# openTPM-v14.net
KiCad netlist of a schematic drawn in EAGLE
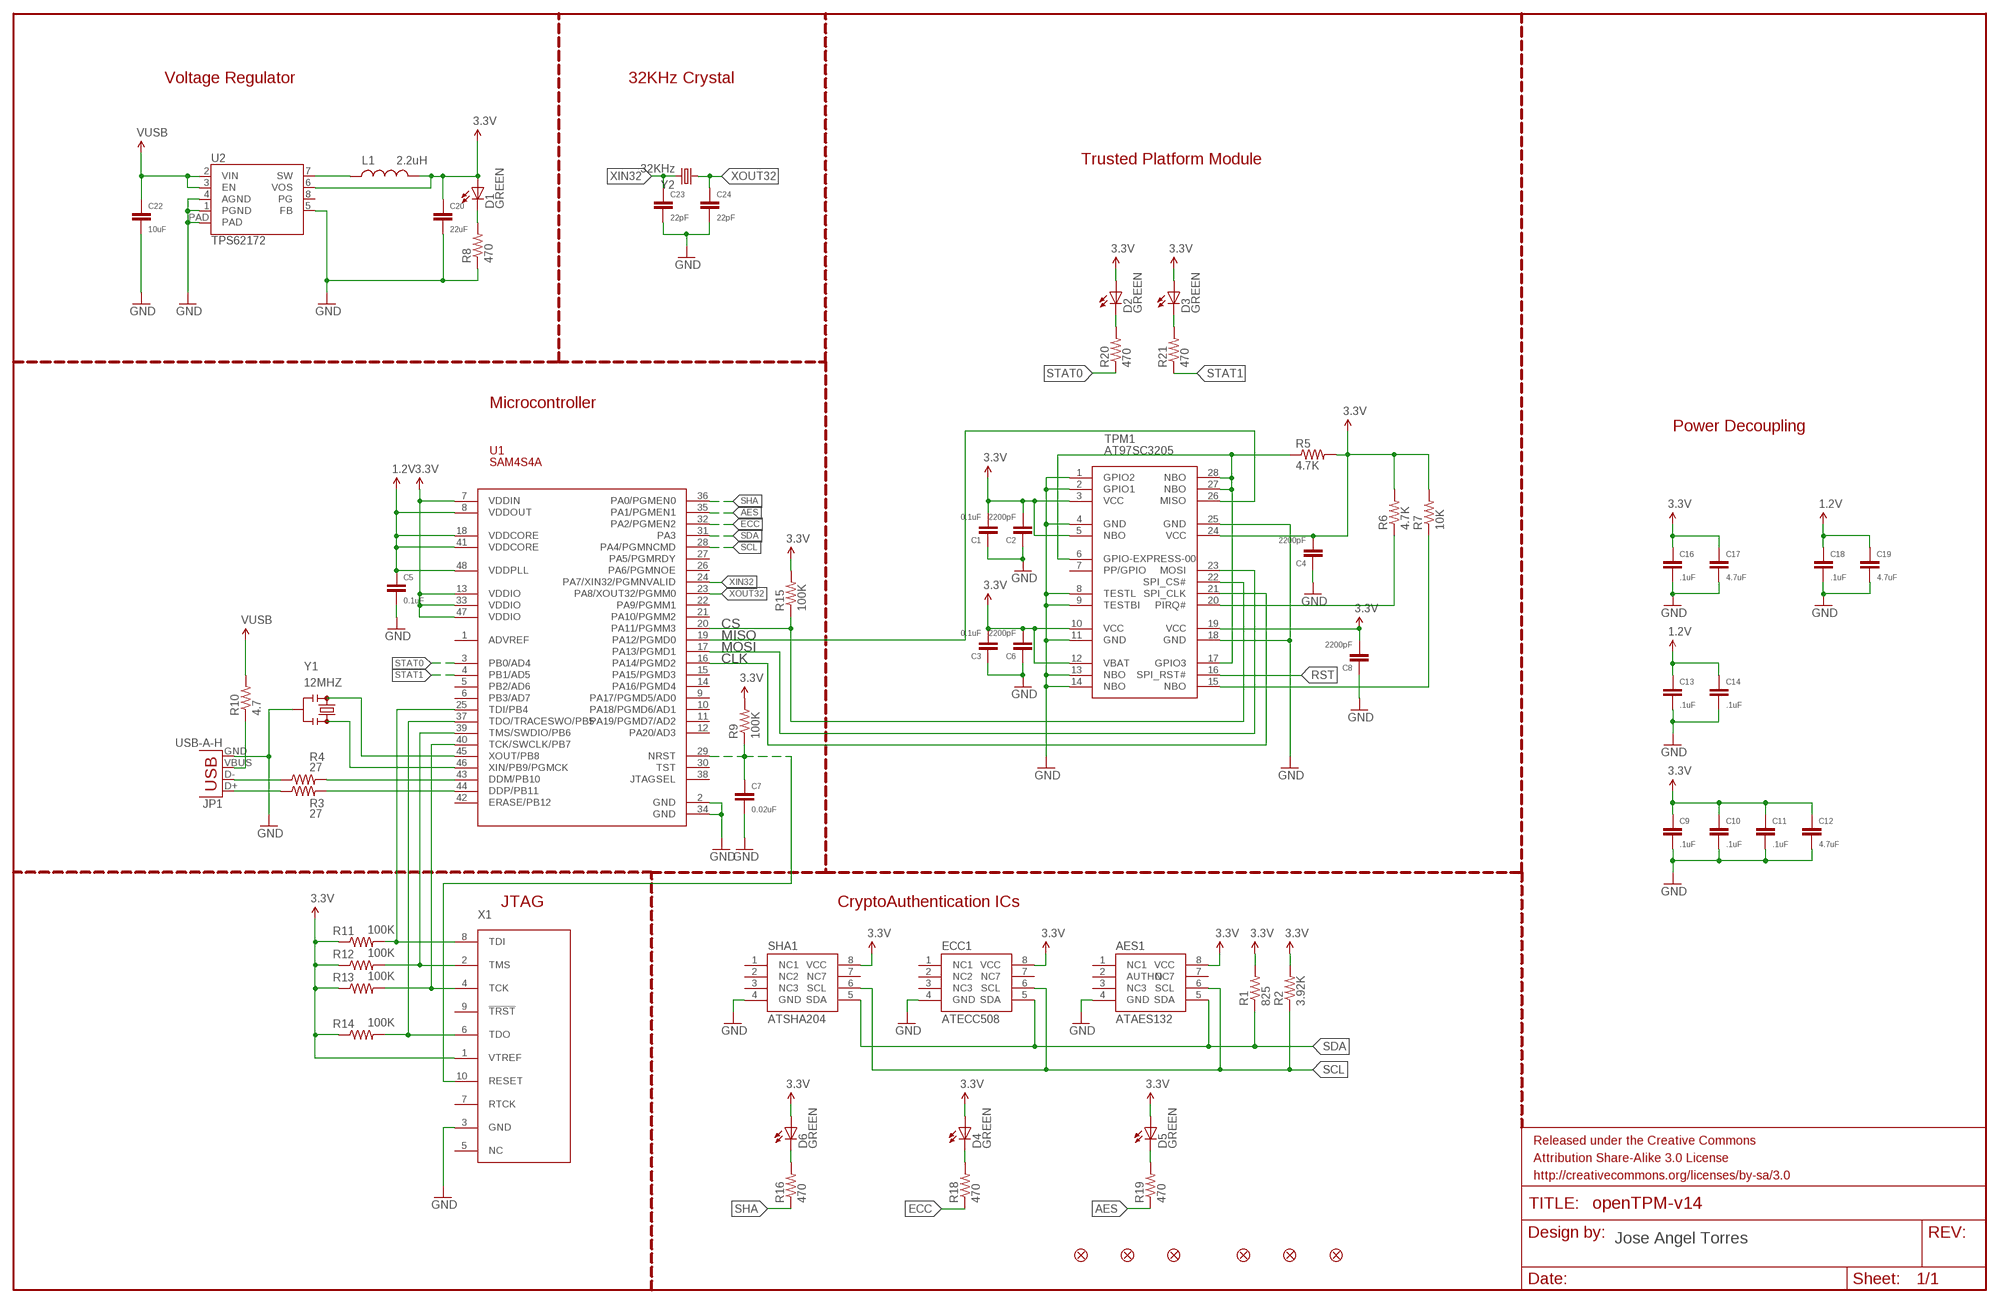
[diagram p0: schematic, sheet 1]

(export (version "E")
  (design (tool "Eeschema 10.0.6"))
  (components
    (comp (ref "AES1")
      (value "ATAES132")
      (footprint "eagle-import:CRYPTOTRONIX_SOIC8")
      (libsource (lib "eagle-import") (part "CRYPTOTRONIX_ATAES132"))
    )
    (comp (ref "C1")
      (value "0.1uF")
      (footprint "eagle-import:0402")
      (libsource (lib "eagle-import") (part "CAPACITOR.0402"))
    )
    (comp (ref "C2")
      (value "2200pF")
      (footprint "eagle-import:0402")
      (libsource (lib "eagle-import") (part "CAPACITOR.0402"))
    )
    (comp (ref "C3")
      (value "0.1uF")
      (footprint "eagle-import:0402")
      (libsource (lib "eagle-import") (part "CAPACITOR.0402"))
    )
    (comp (ref "C4")
      (value "2200pF")
      (footprint "eagle-import:0402")
      (libsource (lib "eagle-import") (part "CAPACITOR.0402"))
    )
    (comp (ref "C5")
      (value "0.1uF")
      (footprint "eagle-import:0402")
      (libsource (lib "eagle-import") (part "CAPACITOR.0402"))
    )
    (comp (ref "C6")
      (value "2200pF")
      (footprint "eagle-import:0402")
      (libsource (lib "eagle-import") (part "CAPACITOR.0402"))
    )
    (comp (ref "C7")
      (value "0.02uF")
      (footprint "eagle-import:0402")
      (libsource (lib "eagle-import") (part "CAPACITOR.0402"))
    )
    (comp (ref "C8")
      (value "2200pF")
      (footprint "eagle-import:0402")
      (libsource (lib "eagle-import") (part "CAPACITOR.0402"))
    )
    (comp (ref "C9")
      (value ".1uF")
      (footprint "eagle-import:0402")
      (libsource (lib "eagle-import") (part "CAPACITOR.0402"))
    )
    (comp (ref "C10")
      (value ".1uF")
      (footprint "eagle-import:0402")
      (libsource (lib "eagle-import") (part "CAPACITOR.0402"))
    )
    (comp (ref "C11")
      (value ".1uF")
      (footprint "eagle-import:0402")
      (libsource (lib "eagle-import") (part "CAPACITOR.0402"))
    )
    (comp (ref "C12")
      (value "4.7uF")
      (footprint "eagle-import:0402")
      (libsource (lib "eagle-import") (part "CAPACITOR.0402"))
    )
    (comp (ref "C13")
      (value ".1uF")
      (footprint "eagle-import:0402")
      (libsource (lib "eagle-import") (part "CAPACITOR.0402"))
    )
    (comp (ref "C14")
      (value ".1uF")
      (footprint "eagle-import:0402")
      (libsource (lib "eagle-import") (part "CAPACITOR.0402"))
    )
    (comp (ref "C16")
      (value ".1uF")
      (footprint "eagle-import:0402")
      (libsource (lib "eagle-import") (part "CAPACITOR.0402"))
    )
    (comp (ref "C17")
      (value "4.7uF")
      (footprint "eagle-import:0402")
      (libsource (lib "eagle-import") (part "CAPACITOR.0402"))
    )
    (comp (ref "C18")
      (value ".1uF")
      (footprint "eagle-import:0402")
      (libsource (lib "eagle-import") (part "CAPACITOR.0402"))
    )
    (comp (ref "C19")
      (value "4.7uF")
      (footprint "eagle-import:0402")
      (libsource (lib "eagle-import") (part "CAPACITOR.0402"))
    )
    (comp (ref "C20")
      (value "22uF")
      (footprint "eagle-import:0603")
      (libsource (lib "eagle-import") (part "CAPACITOR.0603"))
    )
    (comp (ref "C22")
      (value "10uF")
      (footprint "eagle-import:0402")
      (libsource (lib "eagle-import") (part "CAPACITOR.0402"))
    )
    (comp (ref "C23")
      (value "22pF")
      (footprint "eagle-import:0402")
      (libsource (lib "eagle-import") (part "CAPACITOR.0402"))
    )
    (comp (ref "C24")
      (value "22pF")
      (footprint "eagle-import:0402")
      (libsource (lib "eagle-import") (part "CAPACITOR.0402"))
    )
    (comp (ref "D1")
      (value "GREEN")
      (footprint "eagle-import:SPARKFUN-LED_LED-0603")
      (libsource (lib "eagle-import") (part "SPARKFUN-LED_LED-GREEN0603"))
    )
    (comp (ref "D2")
      (value "GREEN")
      (footprint "eagle-import:SPARKFUN-LED_LED-0603")
      (libsource (lib "eagle-import") (part "SPARKFUN-LED_LED-GREEN0603"))
    )
    (comp (ref "D3")
      (value "GREEN")
      (footprint "eagle-import:SPARKFUN-LED_LED-0603")
      (libsource (lib "eagle-import") (part "SPARKFUN-LED_LED-GREEN0603"))
    )
    (comp (ref "D4")
      (value "GREEN")
      (footprint "eagle-import:SPARKFUN-LED_LED-0603")
      (libsource (lib "eagle-import") (part "SPARKFUN-LED_LED-GREEN0603"))
    )
    (comp (ref "D5")
      (value "GREEN")
      (footprint "eagle-import:SPARKFUN-LED_LED-0603")
      (libsource (lib "eagle-import") (part "SPARKFUN-LED_LED-GREEN0603"))
    )
    (comp (ref "D6")
      (value "GREEN")
      (footprint "eagle-import:SPARKFUN-LED_LED-0603")
      (libsource (lib "eagle-import") (part "SPARKFUN-LED_LED-GREEN0603"))
    )
    (comp (ref "ECC1")
      (value "ATECC508")
      (footprint "eagle-import:CRYPTOTRONIX_SOIC8")
      (libsource (lib "eagle-import") (part "ATECC508"))
    )
    (comp (ref "FID1")
      (value "SPARKFUN-AESTHETICS_FIDUCIAL1X2")
      (footprint "eagle-import:SPARKFUN-AESTHETICS_FIDUCIAL-1X2")
      (libsource (lib "eagle-import") (part "SPARKFUN-AESTHETICS_FIDUCIAL1X2"))
    )
    (comp (ref "FID2")
      (value "SPARKFUN-AESTHETICS_FIDUCIAL1X2")
      (footprint "eagle-import:SPARKFUN-AESTHETICS_FIDUCIAL-1X2")
      (libsource (lib "eagle-import") (part "SPARKFUN-AESTHETICS_FIDUCIAL1X2"))
    )
    (comp (ref "FID3")
      (value "SPARKFUN-AESTHETICS_FIDUCIAL1X2")
      (footprint "eagle-import:SPARKFUN-AESTHETICS_FIDUCIAL-1X2")
      (libsource (lib "eagle-import") (part "SPARKFUN-AESTHETICS_FIDUCIAL1X2"))
    )
    (comp (ref "FID4")
      (value "SPARKFUN-AESTHETICS_FIDUCIAL1X2")
      (footprint "eagle-import:SPARKFUN-AESTHETICS_FIDUCIAL-1X2")
      (libsource (lib "eagle-import") (part "SPARKFUN-AESTHETICS_FIDUCIAL1X2"))
    )
    (comp (ref "FID5")
      (value "SPARKFUN-AESTHETICS_FIDUCIAL1X2")
      (footprint "eagle-import:SPARKFUN-AESTHETICS_FIDUCIAL-1X2")
      (libsource (lib "eagle-import") (part "SPARKFUN-AESTHETICS_FIDUCIAL1X2"))
    )
    (comp (ref "FID6")
      (value "SPARKFUN-AESTHETICS_FIDUCIAL1X2")
      (footprint "eagle-import:SPARKFUN-AESTHETICS_FIDUCIAL-1X2")
      (libsource (lib "eagle-import") (part "SPARKFUN-AESTHETICS_FIDUCIAL1X2"))
    )
    (comp (ref "JP1")
      (value "USB-A-H")
      (footprint "eagle-import:USB-A-H")
      (libsource (lib "eagle-import") (part "USB-A-H"))
    )
    (comp (ref "L1")
      (value "2.2uH")
      (footprint "eagle-import:C0402")
      (libsource (lib "eagle-import") (part "INDUCTOR0402"))
    )
    (comp (ref "R1")
      (value "825")
      (footprint "eagle-import:0402")
      (libsource (lib "eagle-import") (part "RESISTOR.0402"))
    )
    (comp (ref "R2")
      (value "3.92K")
      (footprint "eagle-import:0402")
      (libsource (lib "eagle-import") (part "RESISTOR.0402"))
    )
    (comp (ref "R3")
      (value "27")
      (footprint "eagle-import:0402")
      (libsource (lib "eagle-import") (part "RESISTOR.0402"))
    )
    (comp (ref "R4")
      (value "27")
      (footprint "eagle-import:0402")
      (libsource (lib "eagle-import") (part "RESISTOR.0402"))
    )
    (comp (ref "R5")
      (value "4.7K")
      (footprint "eagle-import:0402")
      (libsource (lib "eagle-import") (part "RESISTOR.0402"))
    )
    (comp (ref "R6")
      (value "4.7K")
      (footprint "eagle-import:0402")
      (libsource (lib "eagle-import") (part "RESISTOR.0402"))
    )
    (comp (ref "R7")
      (value "10K")
      (footprint "eagle-import:0402")
      (libsource (lib "eagle-import") (part "RESISTOR.0402"))
    )
    (comp (ref "R8")
      (value "470")
      (footprint "eagle-import:0402")
      (libsource (lib "eagle-import") (part "RESISTOR.0402"))
    )
    (comp (ref "R9")
      (value "100K")
      (footprint "eagle-import:0402")
      (libsource (lib "eagle-import") (part "RESISTOR.0402"))
    )
    (comp (ref "R10")
      (value "4.7")
      (footprint "eagle-import:0402")
      (libsource (lib "eagle-import") (part "RESISTOR.0402"))
    )
    (comp (ref "R11")
      (value "100K")
      (footprint "eagle-import:0402")
      (libsource (lib "eagle-import") (part "RESISTOR.0402"))
    )
    (comp (ref "R12")
      (value "100K")
      (footprint "eagle-import:0402")
      (libsource (lib "eagle-import") (part "RESISTOR.0402"))
    )
    (comp (ref "R13")
      (value "100K")
      (footprint "eagle-import:0402")
      (libsource (lib "eagle-import") (part "RESISTOR.0402"))
    )
    (comp (ref "R14")
      (value "100K")
      (footprint "eagle-import:0402")
      (libsource (lib "eagle-import") (part "RESISTOR.0402"))
    )
    (comp (ref "R15")
      (value "100K")
      (footprint "eagle-import:0402")
      (libsource (lib "eagle-import") (part "RESISTOR.0402"))
    )
    (comp (ref "R16")
      (value "470")
      (footprint "eagle-import:0402")
      (libsource (lib "eagle-import") (part "RESISTOR.0402"))
    )
    (comp (ref "R18")
      (value "470")
      (footprint "eagle-import:0402")
      (libsource (lib "eagle-import") (part "RESISTOR.0402"))
    )
    (comp (ref "R19")
      (value "470")
      (footprint "eagle-import:0402")
      (libsource (lib "eagle-import") (part "RESISTOR.0402"))
    )
    (comp (ref "R20")
      (value "470")
      (footprint "eagle-import:0402")
      (libsource (lib "eagle-import") (part "RESISTOR.0402"))
    )
    (comp (ref "R21")
      (value "470")
      (footprint "eagle-import:0402")
      (libsource (lib "eagle-import") (part "RESISTOR.0402"))
    )
    (comp (ref "SHA1")
      (value "ATSHA204")
      (footprint "eagle-import:CRYPTOTRONIX_SOIC8")
      (libsource (lib "eagle-import") (part "CRYPTOTRONIX_ATSHA204"))
    )
    (comp (ref "TPM1")
      (value "AT97SC3205")
      (footprint "eagle-import:TSSOP28")
      (libsource (lib "eagle-import") (part "AT97SC3205"))
    )
    (comp (ref "U1")
      (value "SAM4S4A")
      (footprint "eagle-import:LQFP-48")
      (libsource (lib "eagle-import") (part "SAM4S4A"))
    )
    (comp (ref "U2")
      (value "TPS62172")
      (footprint "eagle-import:WSON-8-PAD")
      (libsource (lib "eagle-import") (part "TPS62172"))
    )
    (comp (ref "X1")
      (value "TC2050-NL-MCP-NL")
      (footprint "eagle-import:TC2030-MCP-NL")
      (libsource (lib "eagle-import") (part "TC2050-NL-MCP-NL"))
    )
    (comp (ref "Y1")
      (value "12MHZ")
      (footprint "eagle-import:RESONATOR-SMD")
      (libsource (lib "eagle-import") (part "RESONATOR12MHZ"))
    )
    (comp (ref "Y2")
      (value "32KHz")
      (footprint "eagle-import:CRYSTAL-32KHZ-SMD_EPSON_MC146")
      (libsource (lib "eagle-import") (part "CRYSTALEPSONMC146"))
    )
  )
  (nets
    (net (code "1") (name "/CLK") (class "Default")
      (node (ref "TPM1") (pin "21") (pinfunction "SPI_CLK_21") (pintype "bidirectional"))
      (node (ref "U1") (pin "16") (pinfunction "PA14/PGMD2_16") (pintype "bidirectional"))
    )
    (net (code "2") (name "/CS") (class "Default")
      (node (ref "R15") (pin "1") (pinfunction "1_1") (pintype "passive"))
      (node (ref "TPM1") (pin "22") (pinfunction "SPI_CS#_22") (pintype "power_in"))
      (node (ref "U1") (pin "20") (pinfunction "PA11/PGMM3_20") (pintype "bidirectional"))
    )
    (net (code "3") (name "/MISO") (class "Default")
      (node (ref "TPM1") (pin "26") (pinfunction "MISO_26") (pintype "power_in"))
      (node (ref "U1") (pin "19") (pinfunction "PA12/PGMD0_19") (pintype "bidirectional"))
    )
    (net (code "4") (name "/MOSI") (class "Default")
      (node (ref "TPM1") (pin "23") (pinfunction "MOSI_23") (pintype "power_in"))
      (node (ref "U1") (pin "17") (pinfunction "PA13/PGMD1_17") (pintype "bidirectional"))
    )
    (net (code "5") (name "1.2V") (class "Default")
      (node (ref "C13") (pin "1") (pinfunction "1_1") (pintype "passive"))
      (node (ref "C14") (pin "1") (pinfunction "1_1") (pintype "passive"))
      (node (ref "C18") (pin "1") (pinfunction "1_1") (pintype "passive"))
      (node (ref "C19") (pin "1") (pinfunction "1_1") (pintype "passive"))
      (node (ref "C5") (pin "1") (pinfunction "1_1") (pintype "passive"))
      (node (ref "U1") (pin "18") (pinfunction "VDDCORE_18") (pintype "bidirectional"))
      (node (ref "U1") (pin "41") (pinfunction "VDDCORE_41") (pintype "bidirectional"))
      (node (ref "U1") (pin "48") (pinfunction "VDDPLL_48") (pintype "bidirectional"))
      (node (ref "U1") (pin "8") (pinfunction "VDDOUT_8") (pintype "bidirectional"))
    )
    (net (code "6") (name "3.3V") (class "Default")
      (node (ref "AES1") (pin "8") (pinfunction "VCC_8") (pintype "power_in"))
      (node (ref "C1") (pin "2") (pinfunction "2_2") (pintype "passive"))
      (node (ref "C10") (pin "1") (pinfunction "1_1") (pintype "passive"))
      (node (ref "C11") (pin "1") (pinfunction "1_1") (pintype "passive"))
      (node (ref "C12") (pin "1") (pinfunction "1_1") (pintype "passive"))
      (node (ref "C16") (pin "1") (pinfunction "1_1") (pintype "passive"))
      (node (ref "C17") (pin "1") (pinfunction "1_1") (pintype "passive"))
      (node (ref "C2") (pin "2") (pinfunction "2_2") (pintype "passive"))
      (node (ref "C20") (pin "1") (pinfunction "1_1") (pintype "passive"))
      (node (ref "C3") (pin "2") (pinfunction "2_2") (pintype "passive"))
      (node (ref "C4") (pin "2") (pinfunction "2_2") (pintype "passive"))
      (node (ref "C6") (pin "2") (pinfunction "2_2") (pintype "passive"))
      (node (ref "C8") (pin "2") (pinfunction "2_2") (pintype "passive"))
      (node (ref "C9") (pin "1") (pinfunction "1_1") (pintype "passive"))
      (node (ref "D1") (pin "A") (pinfunction "A_A") (pintype "passive"))
      (node (ref "D2") (pin "A") (pinfunction "A_A") (pintype "passive"))
      (node (ref "D3") (pin "A") (pinfunction "A_A") (pintype "passive"))
      (node (ref "D4") (pin "A") (pinfunction "A_A") (pintype "passive"))
      (node (ref "D5") (pin "A") (pinfunction "A_A") (pintype "passive"))
      (node (ref "D6") (pin "A") (pinfunction "A_A") (pintype "passive"))
      (node (ref "ECC1") (pin "8") (pinfunction "VCC_8") (pintype "power_in"))
      (node (ref "L1") (pin "2") (pinfunction "2_2") (pintype "passive"))
      (node (ref "R1") (pin "2") (pinfunction "2_2") (pintype "passive"))
      (node (ref "R11") (pin "1") (pinfunction "1_1") (pintype "passive"))
      (node (ref "R12") (pin "1") (pinfunction "1_1") (pintype "passive"))
      (node (ref "R13") (pin "1") (pinfunction "1_1") (pintype "passive"))
      (node (ref "R14") (pin "1") (pinfunction "1_1") (pintype "passive"))
      (node (ref "R15") (pin "2") (pinfunction "2_2") (pintype "passive"))
      (node (ref "R2") (pin "2") (pinfunction "2_2") (pintype "passive"))
      (node (ref "R5") (pin "2") (pinfunction "2_2") (pintype "passive"))
      (node (ref "R6") (pin "2") (pinfunction "2_2") (pintype "passive"))
      (node (ref "R7") (pin "2") (pinfunction "2_2") (pintype "passive"))
      (node (ref "R9") (pin "2") (pinfunction "2_2") (pintype "passive"))
      (node (ref "SHA1") (pin "8") (pinfunction "VCC_8") (pintype "power_in"))
      (node (ref "TPM1") (pin "10") (pinfunction "VCC_10") (pintype "power_in"))
      (node (ref "TPM1") (pin "12") (pinfunction "VBAT_12") (pintype "bidirectional"))
      (node (ref "TPM1") (pin "19") (pinfunction "VCC_19") (pintype "power_in"))
      (node (ref "TPM1") (pin "24") (pinfunction "VCC_24") (pintype "power_in"))
      (node (ref "TPM1") (pin "3") (pinfunction "VCC_3") (pintype "power_in"))
      (node (ref "TPM1") (pin "5") (pinfunction "NBO_5") (pintype "bidirectional"))
      (node (ref "U1") (pin "13") (pinfunction "VDDIO_13") (pintype "bidirectional"))
      (node (ref "U1") (pin "33") (pinfunction "VDDIO_33") (pintype "bidirectional"))
      (node (ref "U1") (pin "47") (pinfunction "VDDIO_47") (pintype "bidirectional"))
      (node (ref "U1") (pin "7") (pinfunction "VDDIN_7") (pintype "bidirectional"))
      (node (ref "U2") (pin "6") (pinfunction "VOS_6") (pintype "bidirectional"))
      (node (ref "X1") (pin "1") (pinfunction "VTREF_1") (pintype "bidirectional"))
    )
    (net (code "7") (name "AES") (class "Default")
      (node (ref "R19") (pin "1") (pinfunction "1_1") (pintype "passive"))
      (node (ref "U1") (pin "35") (pinfunction "PA1/PGMEN1_35") (pintype "bidirectional"))
    )
    (net (code "8") (name "ECC") (class "Default")
      (node (ref "R18") (pin "1") (pinfunction "1_1") (pintype "passive"))
      (node (ref "U1") (pin "32") (pinfunction "PA2/PGMEN2_32") (pintype "bidirectional"))
    )
    (net (code "9") (name "GND") (class "Default")
      (node (ref "AES1") (pin "4") (pinfunction "GND_4") (pintype "power_in"))
      (node (ref "C1") (pin "1") (pinfunction "1_1") (pintype "passive"))
      (node (ref "C10") (pin "2") (pinfunction "2_2") (pintype "passive"))
      (node (ref "C11") (pin "2") (pinfunction "2_2") (pintype "passive"))
      (node (ref "C12") (pin "2") (pinfunction "2_2") (pintype "passive"))
      (node (ref "C13") (pin "2") (pinfunction "2_2") (pintype "passive"))
      (node (ref "C14") (pin "2") (pinfunction "2_2") (pintype "passive"))
      (node (ref "C16") (pin "2") (pinfunction "2_2") (pintype "passive"))
      (node (ref "C17") (pin "2") (pinfunction "2_2") (pintype "passive"))
      (node (ref "C18") (pin "2") (pinfunction "2_2") (pintype "passive"))
      (node (ref "C19") (pin "2") (pinfunction "2_2") (pintype "passive"))
      (node (ref "C2") (pin "1") (pinfunction "1_1") (pintype "passive"))
      (node (ref "C20") (pin "2") (pinfunction "2_2") (pintype "passive"))
      (node (ref "C22") (pin "2") (pinfunction "2_2") (pintype "passive"))
      (node (ref "C23") (pin "2") (pinfunction "2_2") (pintype "passive"))
      (node (ref "C24") (pin "2") (pinfunction "2_2") (pintype "passive"))
      (node (ref "C3") (pin "1") (pinfunction "1_1") (pintype "passive"))
      (node (ref "C4") (pin "1") (pinfunction "1_1") (pintype "passive"))
      (node (ref "C5") (pin "2") (pinfunction "2_2") (pintype "passive"))
      (node (ref "C6") (pin "1") (pinfunction "1_1") (pintype "passive"))
      (node (ref "C7") (pin "2") (pinfunction "2_2") (pintype "passive"))
      (node (ref "C8") (pin "1") (pinfunction "1_1") (pintype "passive"))
      (node (ref "C9") (pin "2") (pinfunction "2_2") (pintype "passive"))
      (node (ref "ECC1") (pin "4") (pinfunction "GND_4") (pintype "power_in"))
      (node (ref "JP1") (pin "GND") (pinfunction "GND_GND") (pintype "bidirectional"))
      (node (ref "R8") (pin "1") (pinfunction "1_1") (pintype "passive"))
      (node (ref "SHA1") (pin "4") (pinfunction "GND_4") (pintype "power_in"))
      (node (ref "TPM1") (pin "1") (pinfunction "GPIO2_1") (pintype "bidirectional"))
      (node (ref "TPM1") (pin "11") (pinfunction "GND_11") (pintype "power_in"))
      (node (ref "TPM1") (pin "13") (pinfunction "NBO_13") (pintype "bidirectional"))
      (node (ref "TPM1") (pin "14") (pinfunction "NBO_14") (pintype "bidirectional"))
      (node (ref "TPM1") (pin "18") (pinfunction "GND_18") (pintype "power_in"))
      (node (ref "TPM1") (pin "2") (pinfunction "GPIO1_2") (pintype "bidirectional"))
      (node (ref "TPM1") (pin "25") (pinfunction "GND_25") (pintype "power_in"))
      (node (ref "TPM1") (pin "4") (pinfunction "GND_4") (pintype "power_in"))
      (node (ref "TPM1") (pin "8") (pinfunction "TESTL_8") (pintype "bidirectional"))
      (node (ref "TPM1") (pin "9") (pinfunction "TESTBI_9") (pintype "bidirectional"))
      (node (ref "U1") (pin "2") (pinfunction "GND_2") (pintype "bidirectional"))
      (node (ref "U1") (pin "34") (pinfunction "GND_34") (pintype "bidirectional"))
      (node (ref "U2") (pin "1") (pinfunction "PGND_1") (pintype "bidirectional"))
      (node (ref "U2") (pin "4") (pinfunction "AGND_4") (pintype "bidirectional"))
      (node (ref "U2") (pin "5") (pinfunction "FB_5") (pintype "bidirectional"))
      (node (ref "U2") (pin "PAD") (pinfunction "PAD_PAD") (pintype "bidirectional"))
      (node (ref "X1") (pin "3") (pinfunction "GND_3") (pintype "bidirectional"))
      (node (ref "Y1") (pin "2") (pinfunction "2_2") (pintype "passive"))
    )
    (net (code "10") (name "Net-(D1-PadC)") (class "Default")
      (node (ref "D1") (pin "C") (pinfunction "C_C") (pintype "passive"))
      (node (ref "R8") (pin "2") (pinfunction "2_2") (pintype "passive"))
    )
    (net (code "11") (name "Net-(D2-PadC)") (class "Default")
      (node (ref "D2") (pin "C") (pinfunction "C_C") (pintype "passive"))
      (node (ref "R20") (pin "2") (pinfunction "2_2") (pintype "passive"))
    )
    (net (code "12") (name "Net-(D3-PadC)") (class "Default")
      (node (ref "D3") (pin "C") (pinfunction "C_C") (pintype "passive"))
      (node (ref "R21") (pin "2") (pinfunction "2_2") (pintype "passive"))
    )
    (net (code "13") (name "Net-(D4-PadC)") (class "Default")
      (node (ref "D4") (pin "C") (pinfunction "C_C") (pintype "passive"))
      (node (ref "R18") (pin "2") (pinfunction "2_2") (pintype "passive"))
    )
    (net (code "14") (name "Net-(D5-PadC)") (class "Default")
      (node (ref "D5") (pin "C") (pinfunction "C_C") (pintype "passive"))
      (node (ref "R19") (pin "2") (pinfunction "2_2") (pintype "passive"))
    )
    (net (code "15") (name "Net-(D6-PadC)") (class "Default")
      (node (ref "D6") (pin "C") (pinfunction "C_C") (pintype "passive"))
      (node (ref "R16") (pin "2") (pinfunction "2_2") (pintype "passive"))
    )
    (net (code "16") (name "Net-(JP1-PadD+)") (class "Default")
      (node (ref "JP1") (pin "D+") (pinfunction "D+_D+") (pintype "bidirectional"))
      (node (ref "R3") (pin "1") (pinfunction "1_1") (pintype "passive"))
    )
    (net (code "17") (name "Net-(JP1-PadD-)") (class "Default")
      (node (ref "JP1") (pin "D-") (pinfunction "D-_D-") (pintype "bidirectional"))
      (node (ref "R4") (pin "1") (pinfunction "1_1") (pintype "passive"))
    )
    (net (code "18") (name "Net-(JP1-PadVBUS)") (class "Default")
      (node (ref "JP1") (pin "VBUS") (pinfunction "VBUS_VBUS") (pintype "bidirectional"))
      (node (ref "R10") (pin "1") (pinfunction "1_1") (pintype "passive"))
    )
    (net (code "19") (name "Net-(R7-Pad1)") (class "Default")
      (node (ref "R7") (pin "1") (pinfunction "1_1") (pintype "passive"))
      (node (ref "TPM1") (pin "15") (pinfunction "NBO_15") (pintype "bidirectional"))
    )
    (net (code "20") (name "Net-(TPM1-GPIO-EXPRESS-00)") (class "Default")
      (node (ref "R5") (pin "1") (pinfunction "1_1") (pintype "passive"))
      (node (ref "TPM1") (pin "17") (pinfunction "GPIO3_17") (pintype "power_in"))
      (node (ref "TPM1") (pin "27") (pinfunction "NBO_27") (pintype "bidirectional"))
      (node (ref "TPM1") (pin "28") (pinfunction "NBO_28") (pintype "bidirectional"))
      (node (ref "TPM1") (pin "6") (pinfunction "GPIO-EXPRESS-00_6") (pintype "power_in"))
    )
    (net (code "21") (name "Net-(TPM1-PIRQ#)") (class "Default")
      (node (ref "R6") (pin "1") (pinfunction "1_1") (pintype "passive"))
      (node (ref "TPM1") (pin "20") (pinfunction "PIRQ#_20") (pintype "power_in"))
    )
    (net (code "22") (name "Net-(U1-DDM{slash}PB10)") (class "Default")
      (node (ref "R4") (pin "2") (pinfunction "2_2") (pintype "passive"))
      (node (ref "U1") (pin "43") (pinfunction "DDM/PB10_43") (pintype "bidirectional"))
    )
    (net (code "23") (name "Net-(U1-DDP{slash}PB11)") (class "Default")
      (node (ref "R3") (pin "2") (pinfunction "2_2") (pintype "passive"))
      (node (ref "U1") (pin "44") (pinfunction "DDP/PB11_44") (pintype "bidirectional"))
    )
    (net (code "24") (name "Net-(U1-TCK{slash}SWCLK{slash}PB7)") (class "Default")
      (node (ref "R13") (pin "2") (pinfunction "2_2") (pintype "passive"))
      (node (ref "U1") (pin "40") (pinfunction "TCK/SWCLK/PB7_40") (pintype "bidirectional"))
      (node (ref "X1") (pin "4") (pinfunction "TCK_4") (pintype "bidirectional"))
    )
    (net (code "25") (name "Net-(U1-TDI{slash}PB4)") (class "Default")
      (node (ref "R11") (pin "2") (pinfunction "2_2") (pintype "passive"))
      (node (ref "U1") (pin "25") (pinfunction "TDI/PB4_25") (pintype "bidirectional"))
      (node (ref "X1") (pin "8") (pinfunction "TDI_8") (pintype "bidirectional"))
    )
    (net (code "26") (name "Net-(U1-TDO{slash}TRACESWO{slash}PB5)") (class "Default")
      (node (ref "R14") (pin "2") (pinfunction "2_2") (pintype "passive"))
      (node (ref "U1") (pin "37") (pinfunction "TDO/TRACESWO/PB5_37") (pintype "bidirectional"))
      (node (ref "X1") (pin "6") (pinfunction "TDO_6") (pintype "bidirectional"))
    )
    (net (code "27") (name "Net-(U1-TMS{slash}SWDIO{slash}PB6)") (class "Default")
      (node (ref "R12") (pin "2") (pinfunction "2_2") (pintype "passive"))
      (node (ref "U1") (pin "39") (pinfunction "TMS/SWDIO/PB6_39") (pintype "bidirectional"))
      (node (ref "X1") (pin "2") (pinfunction "TMS_2") (pintype "bidirectional"))
    )
    (net (code "28") (name "Net-(U1-XIN{slash}PB9{slash}PGMCK)") (class "Default")
      (node (ref "U1") (pin "46") (pinfunction "XIN/PB9/PGMCK_46") (pintype "bidirectional"))
      (node (ref "Y1") (pin "3") (pinfunction "3_3") (pintype "passive"))
    )
    (net (code "29") (name "Net-(U1-XOUT{slash}PB8)") (class "Default")
      (node (ref "U1") (pin "45") (pinfunction "XOUT/PB8_45") (pintype "bidirectional"))
      (node (ref "Y1") (pin "1") (pinfunction "1_1") (pintype "passive"))
    )
    (net (code "30") (name "Net-(U2-SW)") (class "Default")
      (node (ref "L1") (pin "1") (pinfunction "1_1") (pintype "passive"))
      (node (ref "U2") (pin "7") (pinfunction "SW_7") (pintype "bidirectional"))
    )
    (net (code "31") (name "RST") (class "Default")
      (node (ref "C7") (pin "1") (pinfunction "1_1") (pintype "passive"))
      (node (ref "R9") (pin "1") (pinfunction "1_1") (pintype "passive"))
      (node (ref "TPM1") (pin "16") (pinfunction "SPI_RST#_16") (pintype "bidirectional"))
      (node (ref "U1") (pin "29") (pinfunction "NRST_29") (pintype "bidirectional"))
      (node (ref "X1") (pin "10") (pinfunction "RESET_10") (pintype "bidirectional"))
    )
    (net (code "32") (name "SCL") (class "Default")
      (node (ref "AES1") (pin "6") (pinfunction "SCL_6") (pintype "bidirectional"))
      (node (ref "ECC1") (pin "6") (pinfunction "SCL_6") (pintype "bidirectional"))
      (node (ref "R2") (pin "1") (pinfunction "1_1") (pintype "passive"))
      (node (ref "SHA1") (pin "6") (pinfunction "SCL_6") (pintype "bidirectional"))
      (node (ref "U1") (pin "28") (pinfunction "PA4/PGMNCMD_28") (pintype "bidirectional"))
    )
    (net (code "33") (name "SDA") (class "Default")
      (node (ref "AES1") (pin "5") (pinfunction "SDA_5") (pintype "bidirectional"))
      (node (ref "ECC1") (pin "5") (pinfunction "SDA_5") (pintype "bidirectional"))
      (node (ref "R1") (pin "1") (pinfunction "1_1") (pintype "passive"))
      (node (ref "SHA1") (pin "5") (pinfunction "SDA_5") (pintype "bidirectional"))
      (node (ref "U1") (pin "31") (pinfunction "PA3_31") (pintype "bidirectional"))
    )
    (net (code "34") (name "SHA") (class "Default")
      (node (ref "R16") (pin "1") (pinfunction "1_1") (pintype "passive"))
      (node (ref "U1") (pin "36") (pinfunction "PA0/PGMEN0_36") (pintype "bidirectional"))
    )
    (net (code "35") (name "STAT0") (class "Default")
      (node (ref "R20") (pin "1") (pinfunction "1_1") (pintype "passive"))
      (node (ref "U1") (pin "3") (pinfunction "PB0/AD4_3") (pintype "bidirectional"))
    )
    (net (code "36") (name "STAT1") (class "Default")
      (node (ref "R21") (pin "1") (pinfunction "1_1") (pintype "passive"))
      (node (ref "U1") (pin "4") (pinfunction "PB1/AD5_4") (pintype "bidirectional"))
    )
    (net (code "37") (name "VUSB") (class "Default")
      (node (ref "C22") (pin "1") (pinfunction "1_1") (pintype "passive"))
      (node (ref "R10") (pin "2") (pinfunction "2_2") (pintype "passive"))
      (node (ref "U2") (pin "2") (pinfunction "VIN_2") (pintype "bidirectional"))
      (node (ref "U2") (pin "3") (pinfunction "EN_3") (pintype "bidirectional"))
    )
    (net (code "38") (name "XIN32") (class "Default")
      (node (ref "C23") (pin "1") (pinfunction "1_1") (pintype "passive"))
      (node (ref "U1") (pin "24") (pinfunction "PA7/XIN32/PGMNVALID_24") (pintype "bidirectional"))
      (node (ref "Y2") (pin "P$1") (pinfunction "2_P$1") (pintype "passive"))
    )
    (net (code "39") (name "XOUT32") (class "Default")
      (node (ref "C24") (pin "1") (pinfunction "1_1") (pintype "passive"))
      (node (ref "U1") (pin "23") (pinfunction "PA8/XOUT32/PGMM0_23") (pintype "bidirectional"))
      (node (ref "Y2") (pin "P$2") (pinfunction "1_P$2") (pintype "passive"))
    )
    (net (code "40") (name "unconnected-(AES1-AUTHO-Pad2)") (class "Default")
      (node (ref "AES1") (pin "2") (pinfunction "AUTHO_2") (pintype "bidirectional"))
    )
    (net (code "41") (name "unconnected-(AES1-NC1-Pad1)") (class "Default")
      (node (ref "AES1") (pin "1") (pinfunction "NC1_1") (pintype "no_connect"))
    )
    (net (code "42") (name "unconnected-(AES1-NC3-Pad3)") (class "Default")
      (node (ref "AES1") (pin "3") (pinfunction "NC3_3") (pintype "no_connect"))
    )
    (net (code "43") (name "unconnected-(AES1-NC7-Pad7)") (class "Default")
      (node (ref "AES1") (pin "7") (pinfunction "NC7_7") (pintype "no_connect"))
    )
    (net (code "44") (name "unconnected-(ECC1-NC1-Pad1)") (class "Default")
      (node (ref "ECC1") (pin "1") (pinfunction "NC1_1") (pintype "bidirectional"))
    )
    (net (code "45") (name "unconnected-(ECC1-NC2-Pad2)") (class "Default")
      (node (ref "ECC1") (pin "2") (pinfunction "NC2_2") (pintype "no_connect"))
    )
    (net (code "46") (name "unconnected-(ECC1-NC3-Pad3)") (class "Default")
      (node (ref "ECC1") (pin "3") (pinfunction "NC3_3") (pintype "no_connect"))
    )
    (net (code "47") (name "unconnected-(ECC1-NC7-Pad7)") (class "Default")
      (node (ref "ECC1") (pin "7") (pinfunction "NC7_7") (pintype "no_connect"))
    )
    (net (code "48") (name "unconnected-(SHA1-NC1-Pad1)") (class "Default")
      (node (ref "SHA1") (pin "1") (pinfunction "NC1_1") (pintype "no_connect"))
    )
    (net (code "49") (name "unconnected-(SHA1-NC2-Pad2)") (class "Default")
      (node (ref "SHA1") (pin "2") (pinfunction "NC2_2") (pintype "no_connect"))
    )
    (net (code "50") (name "unconnected-(SHA1-NC3-Pad3)") (class "Default")
      (node (ref "SHA1") (pin "3") (pinfunction "NC3_3") (pintype "no_connect"))
    )
    (net (code "51") (name "unconnected-(SHA1-NC7-Pad7)") (class "Default")
      (node (ref "SHA1") (pin "7") (pinfunction "NC7_7") (pintype "no_connect"))
    )
    (net (code "52") (name "unconnected-(TPM1-PP{slash}GPIO-Pad7)") (class "Default")
      (node (ref "TPM1") (pin "7") (pinfunction "PP/GPIO_7") (pintype "bidirectional"))
    )
    (net (code "53") (name "unconnected-(U1-ADVREF-Pad1)") (class "Default")
      (node (ref "U1") (pin "1") (pinfunction "ADVREF_1") (pintype "bidirectional"))
    )
    (net (code "54") (name "unconnected-(U1-ERASE{slash}PB12-Pad42)") (class "Default")
      (node (ref "U1") (pin "42") (pinfunction "ERASE/PB12_42") (pintype "bidirectional"))
    )
    (net (code "55") (name "unconnected-(U1-JTAGSEL-Pad38)") (class "Default")
      (node (ref "U1") (pin "38") (pinfunction "JTAGSEL_38") (pintype "bidirectional"))
    )
    (net (code "56") (name "unconnected-(U1-PA5{slash}PGMRDY-Pad27)") (class "Default")
      (node (ref "U1") (pin "27") (pinfunction "PA5/PGMRDY_27") (pintype "bidirectional"))
    )
    (net (code "57") (name "unconnected-(U1-PA6{slash}PGMNOE-Pad26)") (class "Default")
      (node (ref "U1") (pin "26") (pinfunction "PA6/PGMNOE_26") (pintype "bidirectional"))
    )
    (net (code "58") (name "unconnected-(U1-PA9{slash}PGMM1-Pad22)") (class "Default")
      (node (ref "U1") (pin "22") (pinfunction "PA9/PGMM1_22") (pintype "bidirectional"))
    )
    (net (code "59") (name "unconnected-(U1-PA10{slash}PGMM2-Pad21)") (class "Default")
      (node (ref "U1") (pin "21") (pinfunction "PA10/PGMM2_21") (pintype "bidirectional"))
    )
    (net (code "60") (name "unconnected-(U1-PA15{slash}PGMD3-Pad15)") (class "Default")
      (node (ref "U1") (pin "15") (pinfunction "PA15/PGMD3_15") (pintype "bidirectional"))
    )
    (net (code "61") (name "unconnected-(U1-PA16{slash}PGMD4-Pad14)") (class "Default")
      (node (ref "U1") (pin "14") (pinfunction "PA16/PGMD4_14") (pintype "bidirectional"))
    )
    (net (code "62") (name "unconnected-(U1-PA17{slash}PGMD5{slash}AD0-Pad9)") (class "Default")
      (node (ref "U1") (pin "9") (pinfunction "PA17/PGMD5/AD0_9") (pintype "bidirectional"))
    )
    (net (code "63") (name "unconnected-(U1-PA18{slash}PGMD6{slash}AD1-Pad10)") (class "Default")
      (node (ref "U1") (pin "10") (pinfunction "PA18/PGMD6/AD1_10") (pintype "bidirectional"))
    )
    (net (code "64") (name "unconnected-(U1-PA19{slash}PGMD7{slash}AD2-Pad11)") (class "Default")
      (node (ref "U1") (pin "11") (pinfunction "PA19/PGMD7/AD2_11") (pintype "bidirectional"))
    )
    (net (code "65") (name "unconnected-(U1-PA20{slash}AD3-Pad12)") (class "Default")
      (node (ref "U1") (pin "12") (pinfunction "PA20/AD3_12") (pintype "bidirectional"))
    )
    (net (code "66") (name "unconnected-(U1-PB2{slash}AD6-Pad5)") (class "Default")
      (node (ref "U1") (pin "5") (pinfunction "PB2/AD6_5") (pintype "bidirectional"))
    )
    (net (code "67") (name "unconnected-(U1-PB3{slash}AD7-Pad6)") (class "Default")
      (node (ref "U1") (pin "6") (pinfunction "PB3/AD7_6") (pintype "bidirectional"))
    )
    (net (code "68") (name "unconnected-(U1-TST-Pad30)") (class "Default")
      (node (ref "U1") (pin "30") (pinfunction "TST_30") (pintype "bidirectional"))
    )
    (net (code "69") (name "unconnected-(U2-PG-Pad8)") (class "Default")
      (node (ref "U2") (pin "8") (pinfunction "PG_8") (pintype "bidirectional"))
    )
    (net (code "70") (name "unconnected-(X1-NC-Pad5)") (class "Default")
      (node (ref "X1") (pin "5") (pinfunction "NC_5") (pintype "bidirectional"))
    )
    (net (code "71") (name "unconnected-(X1-RTCK-Pad7)") (class "Default")
      (node (ref "X1") (pin "7") (pinfunction "RTCK_7") (pintype "bidirectional"))
    )
    (net (code "72") (name "unconnected-(X1-~{TRST}-Pad9)") (class "Default")
      (node (ref "X1") (pin "9") (pinfunction "~{TRST}_9") (pintype "bidirectional"))
    )
  )
)
